# Voicecard-4P-v01.net
KiCad netlist of a schematic drawn in EAGLE
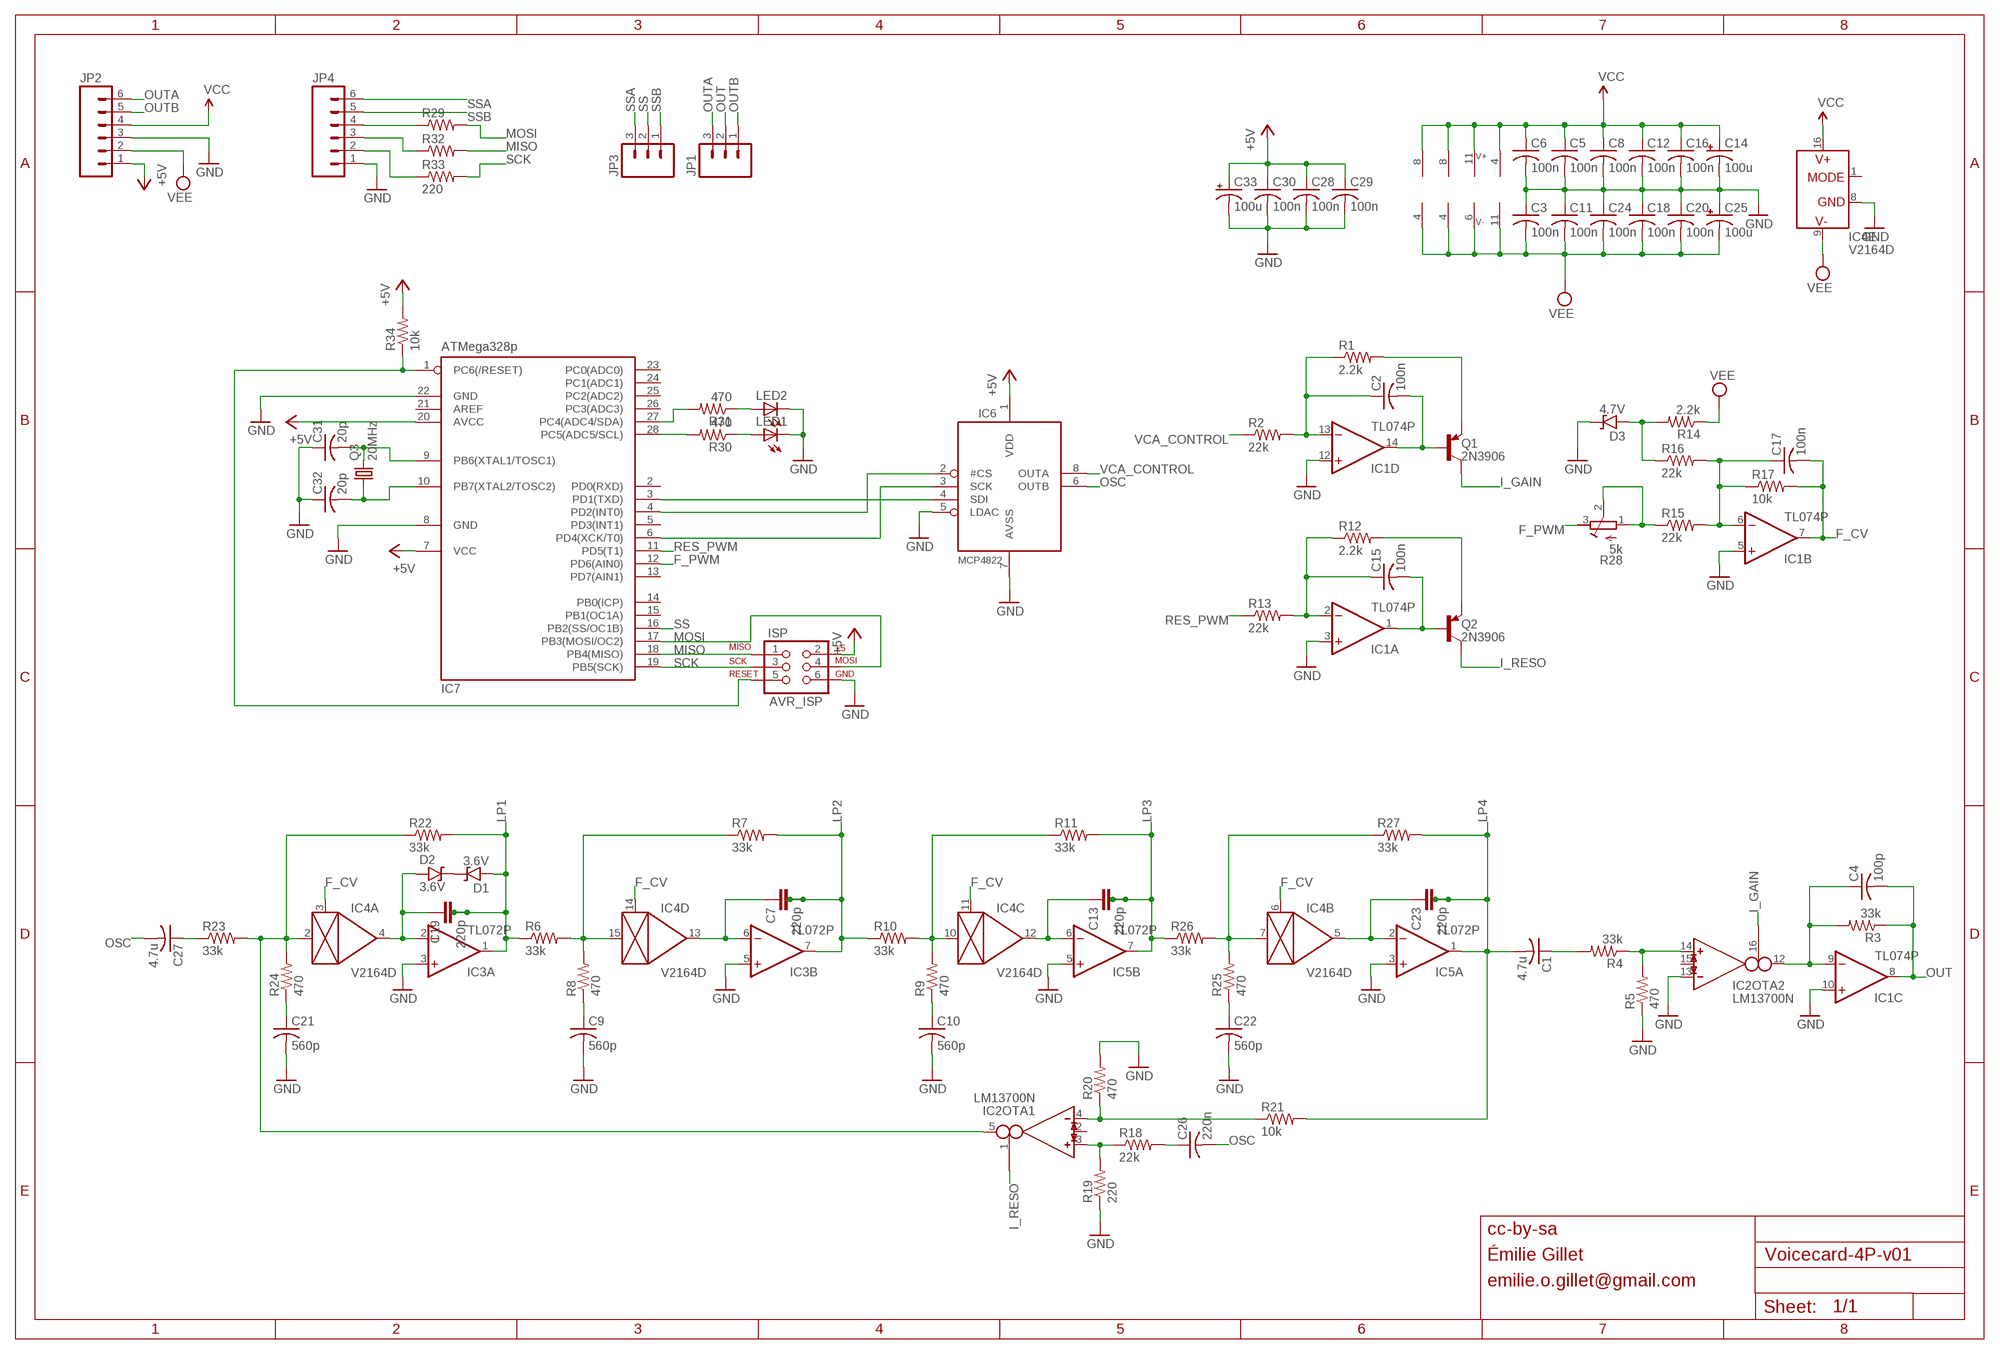
[diagram p0: schematic, sheet 1]

(export (version "E")
  (design (tool "Eeschema 10.0.6"))
  (components
    (comp (ref "C1")
      (value "4.7u")
      (footprint "eagle-import:ENP11-6.3")
      (libsource (lib "eagle-import") (part "C-US"))
    )
    (comp (ref "C2")
      (value "100n")
      (footprint "eagle-import:C025-025X050")
      (libsource (lib "eagle-import") (part "C-US025-025X050"))
    )
    (comp (ref "C3")
      (value "100n")
      (footprint "eagle-import:C025-025X050")
      (libsource (lib "eagle-import") (part "C-US025-025X050"))
    )
    (comp (ref "C4")
      (value "100p")
      (footprint "eagle-import:C025-025X050")
      (libsource (lib "eagle-import") (part "C-US025-025X050"))
    )
    (comp (ref "C5")
      (value "100n")
      (footprint "eagle-import:C025-025X050")
      (libsource (lib "eagle-import") (part "C-US025-025X050"))
    )
    (comp (ref "C6")
      (value "100n")
      (footprint "eagle-import:C025-025X050")
      (libsource (lib "eagle-import") (part "C-US025-025X050"))
    )
    (comp (ref "C7")
      (value "220p")
      (footprint "eagle-import:C2.5_5-4")
      (libsource (lib "eagle-import") (part "C-2.5-5/4"))
    )
    (comp (ref "C8")
      (value "100n")
      (footprint "eagle-import:C025-025X050")
      (libsource (lib "eagle-import") (part "C-US025-025X050"))
    )
    (comp (ref "C9")
      (value "560p")
      (footprint "eagle-import:C025-025X050")
      (libsource (lib "eagle-import") (part "C-US025-025X050"))
    )
    (comp (ref "C10")
      (value "560p")
      (footprint "eagle-import:C025-025X050")
      (libsource (lib "eagle-import") (part "C-US025-025X050"))
    )
    (comp (ref "C11")
      (value "100n")
      (footprint "eagle-import:C025-025X050")
      (libsource (lib "eagle-import") (part "C-US025-025X050"))
    )
    (comp (ref "C12")
      (value "100n")
      (footprint "eagle-import:C025-025X050")
      (libsource (lib "eagle-import") (part "C-US025-025X050"))
    )
    (comp (ref "C13")
      (value "220p")
      (footprint "eagle-import:C2.5_5-4")
      (libsource (lib "eagle-import") (part "C-2.5-5/4"))
    )
    (comp (ref "C14")
      (value "100u")
      (footprint "eagle-import:E2,5-6")
      (libsource (lib "eagle-import") (part "CPOL-USE2.5-6"))
    )
    (comp (ref "C15")
      (value "100n")
      (footprint "eagle-import:C025-025X050")
      (libsource (lib "eagle-import") (part "C-US025-025X050"))
    )
    (comp (ref "C16")
      (value "100n")
      (footprint "eagle-import:C025-025X050")
      (libsource (lib "eagle-import") (part "C-US025-025X050"))
    )
    (comp (ref "C17")
      (value "100n")
      (footprint "eagle-import:C025-025X050")
      (libsource (lib "eagle-import") (part "C-US025-025X050"))
    )
    (comp (ref "C18")
      (value "100n")
      (footprint "eagle-import:C025-025X050")
      (libsource (lib "eagle-import") (part "C-US025-025X050"))
    )
    (comp (ref "C19")
      (value "220p")
      (footprint "eagle-import:C2.5_5-4")
      (libsource (lib "eagle-import") (part "C-2.5-5/4"))
    )
    (comp (ref "C20")
      (value "100n")
      (footprint "eagle-import:C025-025X050")
      (libsource (lib "eagle-import") (part "C-US025-025X050"))
    )
    (comp (ref "C21")
      (value "560p")
      (footprint "eagle-import:C025-025X050")
      (libsource (lib "eagle-import") (part "C-US025-025X050"))
    )
    (comp (ref "C22")
      (value "560p")
      (footprint "eagle-import:C025-025X050")
      (libsource (lib "eagle-import") (part "C-US025-025X050"))
    )
    (comp (ref "C23")
      (value "220p")
      (footprint "eagle-import:C2.5_5-4")
      (libsource (lib "eagle-import") (part "C-2.5-5/4"))
    )
    (comp (ref "C24")
      (value "100n")
      (footprint "eagle-import:C025-025X050")
      (libsource (lib "eagle-import") (part "C-US025-025X050"))
    )
    (comp (ref "C25")
      (value "100u")
      (footprint "eagle-import:E2,5-6")
      (libsource (lib "eagle-import") (part "CPOL-USE2.5-6"))
    )
    (comp (ref "C26")
      (value "220n")
      (footprint "eagle-import:C025-025X050")
      (libsource (lib "eagle-import") (part "C-US025-025X050"))
    )
    (comp (ref "C27")
      (value "4.7u")
      (footprint "eagle-import:ENP11-6.3")
      (libsource (lib "eagle-import") (part "C-US"))
    )
    (comp (ref "C28")
      (value "100n")
      (footprint "eagle-import:C025-025X050")
      (libsource (lib "eagle-import") (part "C-US025-025X050"))
    )
    (comp (ref "C29")
      (value "100n")
      (footprint "eagle-import:C025-025X050")
      (libsource (lib "eagle-import") (part "C-US025-025X050"))
    )
    (comp (ref "C30")
      (value "100n")
      (footprint "eagle-import:C025-025X050")
      (libsource (lib "eagle-import") (part "C-US025-025X050"))
    )
    (comp (ref "C31")
      (value "20p")
      (footprint "eagle-import:C025-025X050")
      (libsource (lib "eagle-import") (part "C-US025-025X050"))
    )
    (comp (ref "C32")
      (value "20p")
      (footprint "eagle-import:C025-025X050")
      (libsource (lib "eagle-import") (part "C-US025-025X050"))
    )
    (comp (ref "C33")
      (value "100u")
      (footprint "eagle-import:E2,5-6")
      (libsource (lib "eagle-import") (part "CPOL-USE2.5-6"))
    )
    (comp (ref "D1")
      (value "3.6V")
      (footprint "eagle-import:D-5")
      (libsource (lib "eagle-import") (part "1N47XXDO35"))
    )
    (comp (ref "D2")
      (value "3.6V")
      (footprint "eagle-import:D-5")
      (libsource (lib "eagle-import") (part "1N47XXDO35"))
    )
    (comp (ref "D3")
      (value "4.7V")
      (footprint "eagle-import:D-5")
      (libsource (lib "eagle-import") (part "1N47XXDO35"))
    )
    (comp (ref "IC1")
      (value "TL074P")
      (footprint "eagle-import:DIL14")
      (libsource (lib "eagle-import") (part "TL074P"))
    )
    (comp (ref "IC2")
      (value "LM13700N")
      (footprint "eagle-import:DIL16")
      (libsource (lib "eagle-import") (part "LM13700N"))
    )
    (comp (ref "IC3")
      (value "TL072P")
      (footprint "eagle-import:DIL08")
      (libsource (lib "eagle-import") (part "TL072P"))
    )
    (comp (ref "IC4")
      (value "V2164D")
      (footprint "eagle-import:DIL16")
      (libsource (lib "eagle-import") (part "SSM2164P"))
    )
    (comp (ref "IC5")
      (value "TL072P")
      (footprint "eagle-import:DIL08")
      (libsource (lib "eagle-import") (part "TL072P"))
    )
    (comp (ref "IC6")
      (value "MCP4822")
      (footprint "eagle-import:DIL08")
      (libsource (lib "eagle-import") (part "MCP4822"))
    )
    (comp (ref "IC7")
      (value "ATMega328p")
      (footprint "eagle-import:DIL28-3")
      (libsource (lib "eagle-import") (part "MEGA8-P"))
    )
    (comp (ref "ISP")
      (value "AVR_ISP")
      (footprint "eagle-import:2X3")
      (libsource (lib "eagle-import") (part "AVR_SPI_PRG_6PTH"))
    )
    (comp (ref "JP1")
      (value "M03PTH")
      (footprint "eagle-import:1X03")
      (libsource (lib "eagle-import") (part "M03PTH"))
    )
    (comp (ref "JP2")
      (value "M06SIP")
      (footprint "eagle-import:1X06")
      (libsource (lib "eagle-import") (part "M06SIP"))
    )
    (comp (ref "JP3")
      (value "M03PTH")
      (footprint "eagle-import:1X03")
      (libsource (lib "eagle-import") (part "M03PTH"))
    )
    (comp (ref "JP4")
      (value "M06SIP")
      (footprint "eagle-import:1X06")
      (libsource (lib "eagle-import") (part "M06SIP"))
    )
    (comp (ref "LED1")
      (value "LED3MM")
      (footprint "eagle-import:LED3MM")
      (libsource (lib "eagle-import") (part "LED3MM"))
    )
    (comp (ref "LED2")
      (value "LED3MM")
      (footprint "eagle-import:LED3MM")
      (libsource (lib "eagle-import") (part "LED3MM"))
    )
    (comp (ref "Q1")
      (value "2N3906")
      (footprint "eagle-import:TO92-")
      (libsource (lib "eagle-import") (part "2N3906-"))
    )
    (comp (ref "Q2")
      (value "2N3906")
      (footprint "eagle-import:TO92-")
      (libsource (lib "eagle-import") (part "2N3906-"))
    )
    (comp (ref "Q3")
      (value "20MHz")
      (footprint "eagle-import:HC49U-V")
      (libsource (lib "eagle-import") (part "CRYSTALHC49U-V"))
    )
    (comp (ref "R1")
      (value "2.2k")
      (footprint "eagle-import:0204_7")
      (libsource (lib "eagle-import") (part "R-US_0204/7"))
    )
    (comp (ref "R2")
      (value "22k")
      (footprint "eagle-import:0204_7")
      (libsource (lib "eagle-import") (part "R-US_0204/7"))
    )
    (comp (ref "R3")
      (value "33k")
      (footprint "eagle-import:0204_7")
      (libsource (lib "eagle-import") (part "R-US_0204/7"))
    )
    (comp (ref "R4")
      (value "33k")
      (footprint "eagle-import:0204_7")
      (libsource (lib "eagle-import") (part "R-US_0204/7"))
    )
    (comp (ref "R5")
      (value "470")
      (footprint "eagle-import:0204_7")
      (libsource (lib "eagle-import") (part "R-US_0204/7"))
    )
    (comp (ref "R6")
      (value "33k")
      (footprint "eagle-import:0204_7")
      (libsource (lib "eagle-import") (part "R-US_0204/7"))
    )
    (comp (ref "R7")
      (value "33k")
      (footprint "eagle-import:0204_7")
      (libsource (lib "eagle-import") (part "R-US_0204/7"))
    )
    (comp (ref "R8")
      (value "470")
      (footprint "eagle-import:0204_7")
      (libsource (lib "eagle-import") (part "R-US_0204/7"))
    )
    (comp (ref "R9")
      (value "470")
      (footprint "eagle-import:0204_7")
      (libsource (lib "eagle-import") (part "R-US_0204/7"))
    )
    (comp (ref "R10")
      (value "33k")
      (footprint "eagle-import:0204_7")
      (libsource (lib "eagle-import") (part "R-US_0204/7"))
    )
    (comp (ref "R11")
      (value "33k")
      (footprint "eagle-import:0204_7")
      (libsource (lib "eagle-import") (part "R-US_0204/7"))
    )
    (comp (ref "R12")
      (value "2.2k")
      (footprint "eagle-import:0204_7")
      (libsource (lib "eagle-import") (part "R-US_0204/7"))
    )
    (comp (ref "R13")
      (value "22k")
      (footprint "eagle-import:0204_7")
      (libsource (lib "eagle-import") (part "R-US_0204/7"))
    )
    (comp (ref "R14")
      (value "2.2k")
      (footprint "eagle-import:0204_7")
      (libsource (lib "eagle-import") (part "R-US_0204/7"))
    )
    (comp (ref "R15")
      (value "22k")
      (footprint "eagle-import:0204_7")
      (libsource (lib "eagle-import") (part "R-US_0204/7"))
    )
    (comp (ref "R16")
      (value "22k")
      (footprint "eagle-import:0204_7")
      (libsource (lib "eagle-import") (part "R-US_0204/7"))
    )
    (comp (ref "R17")
      (value "10k")
      (footprint "eagle-import:0204_7")
      (libsource (lib "eagle-import") (part "R-US_0204/7"))
    )
    (comp (ref "R18")
      (value "22k")
      (footprint "eagle-import:0204_7")
      (libsource (lib "eagle-import") (part "R-US_0204/7"))
    )
    (comp (ref "R19")
      (value "220")
      (footprint "eagle-import:0204_7")
      (libsource (lib "eagle-import") (part "R-US_0204/7"))
    )
    (comp (ref "R20")
      (value "470")
      (footprint "eagle-import:0204_7")
      (libsource (lib "eagle-import") (part "R-US_0204/7"))
    )
    (comp (ref "R21")
      (value "10k")
      (footprint "eagle-import:0204_7")
      (libsource (lib "eagle-import") (part "R-US_0204/7"))
    )
    (comp (ref "R22")
      (value "33k")
      (footprint "eagle-import:0204_7")
      (libsource (lib "eagle-import") (part "R-US_0204/7"))
    )
    (comp (ref "R23")
      (value "33k")
      (footprint "eagle-import:0204_7")
      (libsource (lib "eagle-import") (part "R-US_0204/7"))
    )
    (comp (ref "R24")
      (value "470")
      (footprint "eagle-import:0204_7")
      (libsource (lib "eagle-import") (part "R-US_0204/7"))
    )
    (comp (ref "R25")
      (value "470")
      (footprint "eagle-import:0204_7")
      (libsource (lib "eagle-import") (part "R-US_0204/7"))
    )
    (comp (ref "R26")
      (value "33k")
      (footprint "eagle-import:0204_7")
      (libsource (lib "eagle-import") (part "R-US_0204/7"))
    )
    (comp (ref "R27")
      (value "33k")
      (footprint "eagle-import:0204_7")
      (libsource (lib "eagle-import") (part "R-US_0204/7"))
    )
    (comp (ref "R28")
      (value "5k")
      (footprint "eagle-import:RTRIM3296P")
      (libsource (lib "eagle-import") (part "R-TRIMM3296P"))
    )
    (comp (ref "R29")
      (value "220")
      (footprint "eagle-import:0204_7")
      (libsource (lib "eagle-import") (part "R-US_0204/7"))
    )
    (comp (ref "R30")
      (value "470")
      (footprint "eagle-import:0204_7")
      (libsource (lib "eagle-import") (part "R-US_0204/7"))
    )
    (comp (ref "R31")
      (value "470")
      (footprint "eagle-import:0204_7")
      (libsource (lib "eagle-import") (part "R-US_0204/7"))
    )
    (comp (ref "R32")
      (value "220")
      (footprint "eagle-import:0204_7")
      (libsource (lib "eagle-import") (part "R-US_0204/7"))
    )
    (comp (ref "R33")
      (value "220")
      (footprint "eagle-import:0204_7")
      (libsource (lib "eagle-import") (part "R-US_0204/7"))
    )
    (comp (ref "R34")
      (value "10k")
      (footprint "eagle-import:0204_7")
      (libsource (lib "eagle-import") (part "R-US_0204/7"))
    )
  )
  (nets
    (net (code "1") (name "+5V") (class "Default")
      (node (ref "C28") (pin "1") (pinfunction "1_1") (pintype "passive"))
      (node (ref "C29") (pin "1") (pinfunction "1_1") (pintype "passive"))
      (node (ref "C30") (pin "1") (pinfunction "1_1") (pintype "passive"))
      (node (ref "C33") (pin "+") (pinfunction "+_+") (pintype "passive"))
      (node (ref "IC6") (pin "1") (pinfunction "VDD_1") (pintype "power_in"))
      (node (ref "IC7") (pin "20") (pinfunction "AVCC_20") (pintype "power_in"))
      (node (ref "IC7") (pin "7") (pinfunction "VCC_7") (pintype "power_in"))
      (node (ref "ISP") (pin "2") (pinfunction "2_2") (pintype "passive"))
      (node (ref "JP2") (pin "1") (pinfunction "1_1") (pintype "passive"))
      (node (ref "R34") (pin "2") (pinfunction "2_2") (pintype "passive"))
    )
    (net (code "2") (name "/F_CV") (class "Default")
      (node (ref "C17") (pin "2") (pinfunction "2_2") (pintype "passive"))
      (node (ref "IC1") (pin "7") (pinfunction "OUT_7") (pintype "output"))
      (node (ref "IC4") (pin "11") (pinfunction "CTRL_11") (pintype "input"))
      (node (ref "IC4") (pin "14") (pinfunction "CTRL_14") (pintype "input"))
      (node (ref "IC4") (pin "3") (pinfunction "CTRL_3") (pintype "input"))
      (node (ref "IC4") (pin "6") (pinfunction "CTRL_6") (pintype "input"))
      (node (ref "R17") (pin "2") (pinfunction "2_2") (pintype "passive"))
    )
    (net (code "3") (name "/F_PWM") (class "Default")
      (node (ref "IC7") (pin "12") (pinfunction "PD6(AIN0)_12") (pintype "bidirectional"))
      (node (ref "R28") (pin "3") (pinfunction "A_3") (pintype "passive"))
    )
    (net (code "4") (name "/I_GAIN") (class "Default")
      (node (ref "IC2") (pin "16") (pinfunction "I_BIAS_16") (pintype "input"))
      (node (ref "Q1") (pin "1") (pinfunction "C_1") (pintype "passive"))
    )
    (net (code "5") (name "/I_RESO") (class "Default")
      (node (ref "IC2") (pin "1") (pinfunction "I_BIAS_1") (pintype "input"))
      (node (ref "Q2") (pin "1") (pinfunction "C_1") (pintype "passive"))
    )
    (net (code "6") (name "/LP1") (class "Default")
      (node (ref "C19") (pin "2") (pinfunction "2_2") (pintype "passive"))
      (node (ref "C19") (pin "3") (pinfunction "3_3") (pintype "passive"))
      (node (ref "D1") (pin "A") (pinfunction "A_A") (pintype "passive"))
      (node (ref "IC3") (pin "1") (pinfunction "OUT_1") (pintype "output"))
      (node (ref "R22") (pin "2") (pinfunction "2_2") (pintype "passive"))
      (node (ref "R6") (pin "1") (pinfunction "1_1") (pintype "passive"))
    )
    (net (code "7") (name "/LP2") (class "Default")
      (node (ref "C7") (pin "2") (pinfunction "2_2") (pintype "passive"))
      (node (ref "C7") (pin "3") (pinfunction "3_3") (pintype "passive"))
      (node (ref "IC3") (pin "7") (pinfunction "OUT_7") (pintype "output"))
      (node (ref "R10") (pin "1") (pinfunction "1_1") (pintype "passive"))
      (node (ref "R7") (pin "2") (pinfunction "2_2") (pintype "passive"))
    )
    (net (code "8") (name "/LP3") (class "Default")
      (node (ref "C13") (pin "2") (pinfunction "2_2") (pintype "passive"))
      (node (ref "C13") (pin "3") (pinfunction "3_3") (pintype "passive"))
      (node (ref "IC5") (pin "7") (pinfunction "OUT_7") (pintype "output"))
      (node (ref "R11") (pin "2") (pinfunction "2_2") (pintype "passive"))
      (node (ref "R26") (pin "1") (pinfunction "1_1") (pintype "passive"))
    )
    (net (code "9") (name "/LP4") (class "Default")
      (node (ref "C1") (pin "-") (pinfunction "2_-") (pintype "passive"))
      (node (ref "C23") (pin "2") (pinfunction "2_2") (pintype "passive"))
      (node (ref "C23") (pin "3") (pinfunction "3_3") (pintype "passive"))
      (node (ref "IC5") (pin "1") (pinfunction "OUT_1") (pintype "output"))
      (node (ref "R21") (pin "2") (pinfunction "2_2") (pintype "passive"))
      (node (ref "R27") (pin "2") (pinfunction "2_2") (pintype "passive"))
    )
    (net (code "10") (name "/MISO") (class "Default")
      (node (ref "IC7") (pin "18") (pinfunction "PB4(MISO)_18") (pintype "bidirectional"))
      (node (ref "ISP") (pin "1") (pinfunction "1_1") (pintype "passive"))
      (node (ref "R32") (pin "2") (pinfunction "2_2") (pintype "passive"))
    )
    (net (code "11") (name "/MOSI") (class "Default")
      (node (ref "IC7") (pin "17") (pinfunction "PB3(MOSI/OC2)_17") (pintype "bidirectional"))
      (node (ref "ISP") (pin "4") (pinfunction "4_4") (pintype "passive"))
      (node (ref "R29") (pin "2") (pinfunction "2_2") (pintype "passive"))
    )
    (net (code "12") (name "/OSC") (class "Default")
      (node (ref "C26") (pin "2") (pinfunction "2_2") (pintype "passive"))
      (node (ref "C27") (pin "-") (pinfunction "2_-") (pintype "passive"))
      (node (ref "IC6") (pin "6") (pinfunction "OUTB_6") (pintype "output"))
    )
    (net (code "13") (name "/OUT") (class "Default")
      (node (ref "C4") (pin "2") (pinfunction "2_2") (pintype "passive"))
      (node (ref "IC1") (pin "8") (pinfunction "OUT_8") (pintype "output"))
      (node (ref "JP1") (pin "2") (pinfunction "2_2") (pintype "passive"))
      (node (ref "R3") (pin "1") (pinfunction "1_1") (pintype "passive"))
    )
    (net (code "14") (name "/OUTA") (class "Default")
      (node (ref "JP1") (pin "3") (pinfunction "3_3") (pintype "passive"))
      (node (ref "JP2") (pin "6") (pinfunction "6_6") (pintype "passive"))
    )
    (net (code "15") (name "/OUTB") (class "Default")
      (node (ref "JP1") (pin "1") (pinfunction "1_1") (pintype "passive"))
      (node (ref "JP2") (pin "5") (pinfunction "5_5") (pintype "passive"))
    )
    (net (code "16") (name "/RES_PWM") (class "Default")
      (node (ref "IC7") (pin "11") (pinfunction "PD5(T1)_11") (pintype "bidirectional"))
      (node (ref "R13") (pin "1") (pinfunction "1_1") (pintype "passive"))
    )
    (net (code "17") (name "/SCK") (class "Default")
      (node (ref "IC7") (pin "19") (pinfunction "PB5(SCK)_19") (pintype "bidirectional"))
      (node (ref "ISP") (pin "3") (pinfunction "3_3") (pintype "passive"))
      (node (ref "R33") (pin "2") (pinfunction "2_2") (pintype "passive"))
    )
    (net (code "18") (name "/SS") (class "Default")
      (node (ref "IC7") (pin "16") (pinfunction "PB2(SS/OC1B)_16") (pintype "bidirectional"))
      (node (ref "JP3") (pin "2") (pinfunction "2_2") (pintype "passive"))
    )
    (net (code "19") (name "/SSA") (class "Default")
      (node (ref "JP3") (pin "3") (pinfunction "3_3") (pintype "passive"))
      (node (ref "JP4") (pin "6") (pinfunction "6_6") (pintype "passive"))
    )
    (net (code "20") (name "/SSB") (class "Default")
      (node (ref "JP3") (pin "1") (pinfunction "1_1") (pintype "passive"))
      (node (ref "JP4") (pin "5") (pinfunction "5_5") (pintype "passive"))
    )
    (net (code "21") (name "/VCA_CONTROL") (class "Default")
      (node (ref "IC6") (pin "8") (pinfunction "OUTA_8") (pintype "output"))
      (node (ref "R2") (pin "1") (pinfunction "1_1") (pintype "passive"))
    )
    (net (code "22") (name "GND") (class "Default")
      (node (ref "C10") (pin "2") (pinfunction "2_2") (pintype "passive"))
      (node (ref "C11") (pin "1") (pinfunction "1_1") (pintype "passive"))
      (node (ref "C12") (pin "2") (pinfunction "2_2") (pintype "passive"))
      (node (ref "C14") (pin "-") (pinfunction "-_-") (pintype "passive"))
      (node (ref "C16") (pin "2") (pinfunction "2_2") (pintype "passive"))
      (node (ref "C18") (pin "1") (pinfunction "1_1") (pintype "passive"))
      (node (ref "C20") (pin "1") (pinfunction "1_1") (pintype "passive"))
      (node (ref "C21") (pin "2") (pinfunction "2_2") (pintype "passive"))
      (node (ref "C22") (pin "2") (pinfunction "2_2") (pintype "passive"))
      (node (ref "C24") (pin "1") (pinfunction "1_1") (pintype "passive"))
      (node (ref "C25") (pin "+") (pinfunction "+_+") (pintype "passive"))
      (node (ref "C28") (pin "2") (pinfunction "2_2") (pintype "passive"))
      (node (ref "C29") (pin "2") (pinfunction "2_2") (pintype "passive"))
      (node (ref "C3") (pin "1") (pinfunction "1_1") (pintype "passive"))
      (node (ref "C30") (pin "2") (pinfunction "2_2") (pintype "passive"))
      (node (ref "C31") (pin "1") (pinfunction "1_1") (pintype "passive"))
      (node (ref "C32") (pin "1") (pinfunction "1_1") (pintype "passive"))
      (node (ref "C33") (pin "-") (pinfunction "-_-") (pintype "passive"))
      (node (ref "C5") (pin "2") (pinfunction "2_2") (pintype "passive"))
      (node (ref "C6") (pin "2") (pinfunction "2_2") (pintype "passive"))
      (node (ref "C8") (pin "2") (pinfunction "2_2") (pintype "passive"))
      (node (ref "C9") (pin "2") (pinfunction "2_2") (pintype "passive"))
      (node (ref "D3") (pin "C") (pinfunction "C_C") (pintype "passive"))
      (node (ref "IC1") (pin "10") (pinfunction "+IN_10") (pintype "input"))
      (node (ref "IC1") (pin "12") (pinfunction "+IN_12") (pintype "input"))
      (node (ref "IC1") (pin "3") (pinfunction "+IN_3") (pintype "input"))
      (node (ref "IC1") (pin "5") (pinfunction "+IN_5") (pintype "input"))
      (node (ref "IC2") (pin "13") (pinfunction "IN_N_13") (pintype "input"))
      (node (ref "IC3") (pin "3") (pinfunction "+IN_3") (pintype "input"))
      (node (ref "IC3") (pin "5") (pinfunction "+IN_5") (pintype "input"))
      (node (ref "IC4") (pin "8") (pinfunction "GND_8") (pintype "power_in"))
      (node (ref "IC5") (pin "3") (pinfunction "+IN_3") (pintype "input"))
      (node (ref "IC5") (pin "5") (pinfunction "+IN_5") (pintype "input"))
      (node (ref "IC6") (pin "5") (pinfunction "LDAC_5") (pintype "input"))
      (node (ref "IC6") (pin "7") (pinfunction "AVSS_7") (pintype "power_in"))
      (node (ref "IC7") (pin "22") (pinfunction "GND_22") (pintype "power_in"))
      (node (ref "IC7") (pin "8") (pinfunction "GND_8") (pintype "power_in"))
      (node (ref "ISP") (pin "6") (pinfunction "6_6") (pintype "passive"))
      (node (ref "JP2") (pin "3") (pinfunction "3_3") (pintype "passive"))
      (node (ref "JP4") (pin "1") (pinfunction "1_1") (pintype "passive"))
      (node (ref "LED1") (pin "K") (pinfunction "C_K") (pintype "passive"))
      (node (ref "LED2") (pin "K") (pinfunction "C_K") (pintype "passive"))
      (node (ref "R19") (pin "1") (pinfunction "1_1") (pintype "passive"))
      (node (ref "R20") (pin "2") (pinfunction "2_2") (pintype "passive"))
      (node (ref "R5") (pin "1") (pinfunction "1_1") (pintype "passive"))
    )
    (net (code "23") (name "Net-(C1-1)") (class "Default")
      (node (ref "C1") (pin "+") (pinfunction "1_+") (pintype "passive"))
      (node (ref "R4") (pin "2") (pinfunction "2_2") (pintype "passive"))
    )
    (net (code "24") (name "Net-(C9-Pad1)") (class "Default")
      (node (ref "C9") (pin "1") (pinfunction "1_1") (pintype "passive"))
      (node (ref "R8") (pin "1") (pinfunction "1_1") (pintype "passive"))
    )
    (net (code "25") (name "Net-(C10-Pad1)") (class "Default")
      (node (ref "C10") (pin "1") (pinfunction "1_1") (pintype "passive"))
      (node (ref "R9") (pin "1") (pinfunction "1_1") (pintype "passive"))
    )
    (net (code "26") (name "Net-(C21-Pad1)") (class "Default")
      (node (ref "C21") (pin "1") (pinfunction "1_1") (pintype "passive"))
      (node (ref "R24") (pin "1") (pinfunction "1_1") (pintype "passive"))
    )
    (net (code "27") (name "Net-(C22-Pad1)") (class "Default")
      (node (ref "C22") (pin "1") (pinfunction "1_1") (pintype "passive"))
      (node (ref "R25") (pin "1") (pinfunction "1_1") (pintype "passive"))
    )
    (net (code "28") (name "Net-(C26-Pad1)") (class "Default")
      (node (ref "C26") (pin "1") (pinfunction "1_1") (pintype "passive"))
      (node (ref "R18") (pin "2") (pinfunction "2_2") (pintype "passive"))
    )
    (net (code "29") (name "Net-(C27-1)") (class "Default")
      (node (ref "C27") (pin "+") (pinfunction "1_+") (pintype "passive"))
      (node (ref "R23") (pin "1") (pinfunction "1_1") (pintype "passive"))
    )
    (net (code "30") (name "Net-(D1-PadC)") (class "Default")
      (node (ref "D1") (pin "C") (pinfunction "C_C") (pintype "passive"))
      (node (ref "D2") (pin "C") (pinfunction "C_C") (pintype "passive"))
    )
    (net (code "31") (name "Net-(D3-PadA)") (class "Default")
      (node (ref "D3") (pin "A") (pinfunction "A_A") (pintype "passive"))
      (node (ref "R14") (pin "2") (pinfunction "2_2") (pintype "passive"))
      (node (ref "R16") (pin "1") (pinfunction "1_1") (pintype "passive"))
    )
    (net (code "32") (name "Net-(IC1A--IN)") (class "Default")
      (node (ref "C15") (pin "1") (pinfunction "1_1") (pintype "passive"))
      (node (ref "IC1") (pin "2") (pinfunction "-IN_2") (pintype "input"))
      (node (ref "R12") (pin "1") (pinfunction "1_1") (pintype "passive"))
      (node (ref "R13") (pin "2") (pinfunction "2_2") (pintype "passive"))
    )
    (net (code "33") (name "Net-(IC1A-OUT)") (class "Default")
      (node (ref "C15") (pin "2") (pinfunction "2_2") (pintype "passive"))
      (node (ref "IC1") (pin "1") (pinfunction "OUT_1") (pintype "output"))
      (node (ref "Q2") (pin "2") (pinfunction "B_2") (pintype "passive"))
    )
    (net (code "34") (name "Net-(IC1B--IN)") (class "Default")
      (node (ref "C17") (pin "1") (pinfunction "1_1") (pintype "passive"))
      (node (ref "IC1") (pin "6") (pinfunction "-IN_6") (pintype "input"))
      (node (ref "R15") (pin "2") (pinfunction "2_2") (pintype "passive"))
      (node (ref "R16") (pin "2") (pinfunction "2_2") (pintype "passive"))
      (node (ref "R17") (pin "1") (pinfunction "1_1") (pintype "passive"))
    )
    (net (code "35") (name "Net-(IC1C--IN)") (class "Default")
      (node (ref "C4") (pin "1") (pinfunction "1_1") (pintype "passive"))
      (node (ref "IC1") (pin "9") (pinfunction "-IN_9") (pintype "input"))
      (node (ref "IC2") (pin "12") (pinfunction "OUT_12") (pintype "output"))
      (node (ref "R3") (pin "2") (pinfunction "2_2") (pintype "passive"))
    )
    (net (code "36") (name "Net-(IC1D--IN)") (class "Default")
      (node (ref "C2") (pin "1") (pinfunction "1_1") (pintype "passive"))
      (node (ref "IC1") (pin "13") (pinfunction "-IN_13") (pintype "input"))
      (node (ref "R1") (pin "1") (pinfunction "1_1") (pintype "passive"))
      (node (ref "R2") (pin "2") (pinfunction "2_2") (pintype "passive"))
    )
    (net (code "37") (name "Net-(IC1D-OUT)") (class "Default")
      (node (ref "C2") (pin "2") (pinfunction "2_2") (pintype "passive"))
      (node (ref "IC1") (pin "14") (pinfunction "OUT_14") (pintype "output"))
      (node (ref "Q1") (pin "2") (pinfunction "B_2") (pintype "passive"))
    )
    (net (code "38") (name "Net-(IC2C-IN_N)") (class "Default")
      (node (ref "IC2") (pin "4") (pinfunction "IN_N_4") (pintype "input"))
      (node (ref "R20") (pin "1") (pinfunction "1_1") (pintype "passive"))
      (node (ref "R21") (pin "1") (pinfunction "1_1") (pintype "passive"))
    )
    (net (code "39") (name "Net-(IC2C-IN_P)") (class "Default")
      (node (ref "IC2") (pin "3") (pinfunction "IN_P_3") (pintype "input"))
      (node (ref "R18") (pin "1") (pinfunction "1_1") (pintype "passive"))
      (node (ref "R19") (pin "2") (pinfunction "2_2") (pintype "passive"))
    )
    (net (code "40") (name "Net-(IC2C-OUT)") (class "Default")
      (node (ref "IC2") (pin "5") (pinfunction "OUT_5") (pintype "output"))
      (node (ref "IC4") (pin "2") (pinfunction "IN_2") (pintype "input"))
      (node (ref "R22") (pin "1") (pinfunction "1_1") (pintype "passive"))
      (node (ref "R23") (pin "2") (pinfunction "2_2") (pintype "passive"))
      (node (ref "R24") (pin "2") (pinfunction "2_2") (pintype "passive"))
    )
    (net (code "41") (name "Net-(IC2D-IN_P)") (class "Default")
      (node (ref "IC2") (pin "14") (pinfunction "IN_P_14") (pintype "input"))
      (node (ref "R4") (pin "1") (pinfunction "1_1") (pintype "passive"))
      (node (ref "R5") (pin "2") (pinfunction "2_2") (pintype "passive"))
    )
    (net (code "42") (name "Net-(IC3A--IN)") (class "Default")
      (node (ref "C19") (pin "1") (pinfunction "1_1") (pintype "passive"))
      (node (ref "D2") (pin "A") (pinfunction "A_A") (pintype "passive"))
      (node (ref "IC3") (pin "2") (pinfunction "-IN_2") (pintype "input"))
      (node (ref "IC4") (pin "4") (pinfunction "OUT_4") (pintype "output"))
    )
    (net (code "43") (name "Net-(IC3B--IN)") (class "Default")
      (node (ref "C7") (pin "1") (pinfunction "1_1") (pintype "passive"))
      (node (ref "IC3") (pin "6") (pinfunction "-IN_6") (pintype "input"))
      (node (ref "IC4") (pin "13") (pinfunction "OUT_13") (pintype "output"))
    )
    (net (code "44") (name "Net-(IC4B-IN)") (class "Default")
      (node (ref "IC4") (pin "7") (pinfunction "IN_7") (pintype "input"))
      (node (ref "R25") (pin "2") (pinfunction "2_2") (pintype "passive"))
      (node (ref "R26") (pin "2") (pinfunction "2_2") (pintype "passive"))
      (node (ref "R27") (pin "1") (pinfunction "1_1") (pintype "passive"))
    )
    (net (code "45") (name "Net-(IC4B-OUT)") (class "Default")
      (node (ref "C23") (pin "1") (pinfunction "1_1") (pintype "passive"))
      (node (ref "IC4") (pin "5") (pinfunction "OUT_5") (pintype "output"))
      (node (ref "IC5") (pin "2") (pinfunction "-IN_2") (pintype "input"))
    )
    (net (code "46") (name "Net-(IC4C-IN)") (class "Default")
      (node (ref "IC4") (pin "10") (pinfunction "IN_10") (pintype "input"))
      (node (ref "R10") (pin "2") (pinfunction "2_2") (pintype "passive"))
      (node (ref "R11") (pin "1") (pinfunction "1_1") (pintype "passive"))
      (node (ref "R9") (pin "2") (pinfunction "2_2") (pintype "passive"))
    )
    (net (code "47") (name "Net-(IC4C-OUT)") (class "Default")
      (node (ref "C13") (pin "1") (pinfunction "1_1") (pintype "passive"))
      (node (ref "IC4") (pin "12") (pinfunction "OUT_12") (pintype "output"))
      (node (ref "IC5") (pin "6") (pinfunction "-IN_6") (pintype "input"))
    )
    (net (code "48") (name "Net-(IC4D-IN)") (class "Default")
      (node (ref "IC4") (pin "15") (pinfunction "IN_15") (pintype "input"))
      (node (ref "R6") (pin "2") (pinfunction "2_2") (pintype "passive"))
      (node (ref "R7") (pin "1") (pinfunction "1_1") (pintype "passive"))
      (node (ref "R8") (pin "2") (pinfunction "2_2") (pintype "passive"))
    )
    (net (code "49") (name "Net-(IC6-#CS)") (class "Default")
      (node (ref "IC6") (pin "2") (pinfunction "#CS_2") (pintype "input"))
      (node (ref "IC7") (pin "4") (pinfunction "PD2(INT0)_4") (pintype "bidirectional"))
    )
    (net (code "50") (name "Net-(IC6-SCK)") (class "Default")
      (node (ref "IC6") (pin "3") (pinfunction "SCK_3") (pintype "input"))
      (node (ref "IC7") (pin "6") (pinfunction "PD4(XCK/T0)_6") (pintype "bidirectional"))
    )
    (net (code "51") (name "Net-(IC6-SDI)") (class "Default")
      (node (ref "IC6") (pin "4") (pinfunction "SDI_4") (pintype "input"))
      (node (ref "IC7") (pin "3") (pinfunction "PD1(TXD)_3") (pintype "bidirectional"))
    )
    (net (code "52") (name "Net-(IC7-PB6(XTAL1{slash}TOSC1))") (class "Default")
      (node (ref "C31") (pin "2") (pinfunction "2_2") (pintype "passive"))
      (node (ref "IC7") (pin "9") (pinfunction "PB6(XTAL1/TOSC1)_9") (pintype "bidirectional"))
      (node (ref "Q3") (pin "2") (pinfunction "2_2") (pintype "passive"))
    )
    (net (code "53") (name "Net-(IC7-PB7(XTAL2{slash}TOSC2))") (class "Default")
      (node (ref "C32") (pin "2") (pinfunction "2_2") (pintype "passive"))
      (node (ref "IC7") (pin "10") (pinfunction "PB7(XTAL2/TOSC2)_10") (pintype "bidirectional"))
      (node (ref "Q3") (pin "1") (pinfunction "1_1") (pintype "passive"))
    )
    (net (code "54") (name "Net-(IC7-PC4(ADC4{slash}SDA))") (class "Default")
      (node (ref "IC7") (pin "27") (pinfunction "PC4(ADC4/SDA)_27") (pintype "bidirectional"))
      (node (ref "R31") (pin "2") (pinfunction "2_2") (pintype "passive"))
    )
    (net (code "55") (name "Net-(IC7-PC5(ADC5{slash}SCL))") (class "Default")
      (node (ref "IC7") (pin "28") (pinfunction "PC5(ADC5/SCL)_28") (pintype "bidirectional"))
      (node (ref "R30") (pin "2") (pinfunction "2_2") (pintype "passive"))
    )
    (net (code "56") (name "Net-(IC7-PC6({slash}RESET))") (class "Default")
      (node (ref "IC7") (pin "1") (pinfunction "PC6(/RESET)_1") (pintype "bidirectional"))
      (node (ref "ISP") (pin "5") (pinfunction "5_5") (pintype "passive"))
      (node (ref "R34") (pin "1") (pinfunction "1_1") (pintype "passive"))
    )
    (net (code "57") (name "Net-(JP4-Pad2)") (class "Default")
      (node (ref "JP4") (pin "2") (pinfunction "2_2") (pintype "passive"))
      (node (ref "R33") (pin "1") (pinfunction "1_1") (pintype "passive"))
    )
    (net (code "58") (name "Net-(JP4-Pad3)") (class "Default")
      (node (ref "JP4") (pin "3") (pinfunction "3_3") (pintype "passive"))
      (node (ref "R32") (pin "1") (pinfunction "1_1") (pintype "passive"))
    )
    (net (code "59") (name "Net-(JP4-Pad4)") (class "Default")
      (node (ref "JP4") (pin "4") (pinfunction "4_4") (pintype "passive"))
      (node (ref "R29") (pin "1") (pinfunction "1_1") (pintype "passive"))
    )
    (net (code "60") (name "Net-(LED1-PadA)") (class "Default")
      (node (ref "LED1") (pin "A") (pinfunction "A_A") (pintype "passive"))
      (node (ref "R30") (pin "1") (pinfunction "1_1") (pintype "passive"))
    )
    (net (code "61") (name "Net-(LED2-PadA)") (class "Default")
      (node (ref "LED2") (pin "A") (pinfunction "A_A") (pintype "passive"))
      (node (ref "R31") (pin "1") (pinfunction "1_1") (pintype "passive"))
    )
    (net (code "62") (name "Net-(Q1-E)") (class "Default")
      (node (ref "Q1") (pin "3") (pinfunction "E_3") (pintype "passive"))
      (node (ref "R1") (pin "2") (pinfunction "2_2") (pintype "passive"))
    )
    (net (code "63") (name "Net-(Q2-E)") (class "Default")
      (node (ref "Q2") (pin "3") (pinfunction "E_3") (pintype "passive"))
      (node (ref "R12") (pin "2") (pinfunction "2_2") (pintype "passive"))
    )
    (net (code "64") (name "Net-(R28-E)") (class "Default")
      (node (ref "R15") (pin "1") (pinfunction "1_1") (pintype "passive"))
      (node (ref "R28") (pin "1") (pinfunction "E_1") (pintype "passive"))
      (node (ref "R28") (pin "2") (pinfunction "S_2") (pintype "passive"))
    )
    (net (code "65") (name "VCC") (class "Default")
      (node (ref "C12") (pin "1") (pinfunction "1_1") (pintype "passive"))
      (node (ref "C14") (pin "+") (pinfunction "+_+") (pintype "passive"))
      (node (ref "C16") (pin "1") (pinfunction "1_1") (pintype "passive"))
      (node (ref "C5") (pin "1") (pinfunction "1_1") (pintype "passive"))
      (node (ref "C6") (pin "1") (pinfunction "1_1") (pintype "passive"))
      (node (ref "C8") (pin "1") (pinfunction "1_1") (pintype "passive"))
      (node (ref "IC1") (pin "4") (pinfunction "V+_4") (pintype "power_in"))
      (node (ref "IC2") (pin "11") (pinfunction "V+_11") (pintype "power_in"))
      (node (ref "IC3") (pin "8") (pinfunction "V+_8") (pintype "power_in"))
      (node (ref "IC4") (pin "16") (pinfunction "V+_16") (pintype "power_in"))
      (node (ref "IC5") (pin "8") (pinfunction "V+_8") (pintype "power_in"))
      (node (ref "JP2") (pin "4") (pinfunction "4_4") (pintype "passive"))
    )
    (net (code "66") (name "VEE") (class "Default")
      (node (ref "C11") (pin "2") (pinfunction "2_2") (pintype "passive"))
      (node (ref "C18") (pin "2") (pinfunction "2_2") (pintype "passive"))
      (node (ref "C20") (pin "2") (pinfunction "2_2") (pintype "passive"))
      (node (ref "C24") (pin "2") (pinfunction "2_2") (pintype "passive"))
      (node (ref "C25") (pin "-") (pinfunction "-_-") (pintype "passive"))
      (node (ref "C3") (pin "2") (pinfunction "2_2") (pintype "passive"))
      (node (ref "IC1") (pin "11") (pinfunction "V-_11") (pintype "power_in"))
      (node (ref "IC2") (pin "6") (pinfunction "V-_6") (pintype "power_in"))
      (node (ref "IC3") (pin "4") (pinfunction "V-_4") (pintype "power_in"))
      (node (ref "IC4") (pin "9") (pinfunction "V-_9") (pintype "power_in"))
      (node (ref "IC5") (pin "4") (pinfunction "V-_4") (pintype "power_in"))
      (node (ref "JP2") (pin "2") (pinfunction "2_2") (pintype "passive"))
      (node (ref "R14") (pin "1") (pinfunction "1_1") (pintype "passive"))
    )
    (net (code "67") (name "unconnected-(IC2C-I_DIODE-Pad2)") (class "Default")
      (node (ref "IC2") (pin "2") (pinfunction "I_DIODE_2") (pintype "input"))
    )
    (net (code "68") (name "unconnected-(IC2D-I_DIODE-Pad15)") (class "Default")
      (node (ref "IC2") (pin "15") (pinfunction "I_DIODE_15") (pintype "input"))
    )
    (net (code "69") (name "unconnected-(IC4E-MODE-Pad1)") (class "Default")
      (node (ref "IC4") (pin "1") (pinfunction "MODE_1") (pintype "input"))
    )
    (net (code "70") (name "unconnected-(IC7-AREF-Pad21)") (class "Default")
      (node (ref "IC7") (pin "21") (pinfunction "AREF_21") (pintype "passive"))
    )
    (net (code "71") (name "unconnected-(IC7-PB0(ICP)-Pad14)") (class "Default")
      (node (ref "IC7") (pin "14") (pinfunction "PB0(ICP)_14") (pintype "bidirectional"))
    )
    (net (code "72") (name "unconnected-(IC7-PB1(OC1A)-Pad15)") (class "Default")
      (node (ref "IC7") (pin "15") (pinfunction "PB1(OC1A)_15") (pintype "bidirectional"))
    )
    (net (code "73") (name "unconnected-(IC7-PC0(ADC0)-Pad23)") (class "Default")
      (node (ref "IC7") (pin "23") (pinfunction "PC0(ADC0)_23") (pintype "bidirectional"))
    )
    (net (code "74") (name "unconnected-(IC7-PC1(ADC1)-Pad24)") (class "Default")
      (node (ref "IC7") (pin "24") (pinfunction "PC1(ADC1)_24") (pintype "bidirectional"))
    )
    (net (code "75") (name "unconnected-(IC7-PC2(ADC2)-Pad25)") (class "Default")
      (node (ref "IC7") (pin "25") (pinfunction "PC2(ADC2)_25") (pintype "bidirectional"))
    )
    (net (code "76") (name "unconnected-(IC7-PC3(ADC3)-Pad26)") (class "Default")
      (node (ref "IC7") (pin "26") (pinfunction "PC3(ADC3)_26") (pintype "bidirectional"))
    )
    (net (code "77") (name "unconnected-(IC7-PD0(RXD)-Pad2)") (class "Default")
      (node (ref "IC7") (pin "2") (pinfunction "PD0(RXD)_2") (pintype "bidirectional"))
    )
    (net (code "78") (name "unconnected-(IC7-PD3(INT1)-Pad5)") (class "Default")
      (node (ref "IC7") (pin "5") (pinfunction "PD3(INT1)_5") (pintype "bidirectional"))
    )
    (net (code "79") (name "unconnected-(IC7-PD7(AIN1)-Pad13)") (class "Default")
      (node (ref "IC7") (pin "13") (pinfunction "PD7(AIN1)_13") (pintype "bidirectional"))
    )
  )
)
